# ADC.net
KiCad netlist of a schematic drawn in Altium Designer
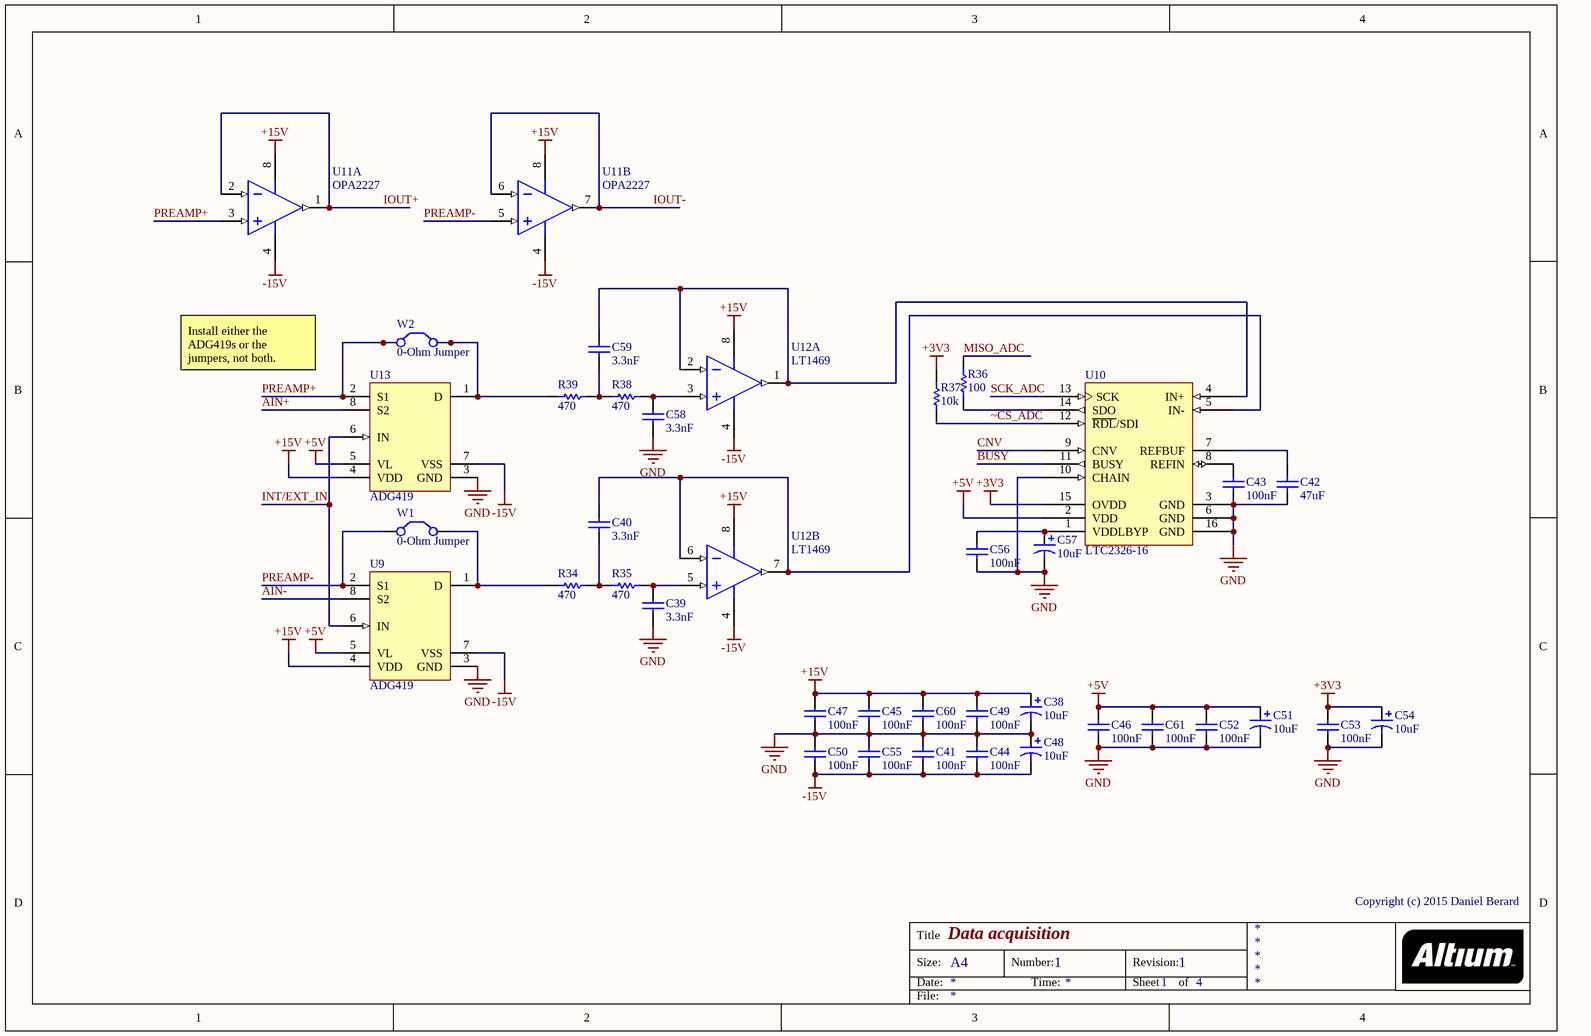
[diagram p0: ADC.SchDoc]

(export (version "E")
  (design (tool "Eeschema 10.0.6"))
  (components
    (comp (ref "C38")
      (value "10uF")
      (footprint "3528")
      (description "Polarized Capacitor (Radial)")
      (fields (field (name "PUBLISHER") "Altium Limited"))
      (libsource (lib "Miscellaneous Devices") (part "Cap Pol1"))
    )
    (comp (ref "C39")
      (value "3.3nF")
      (footprint "6-0805_N")
      (description "Capacitor")
      (fields (field (name "PUBLISHER") "Altium Limited"))
      (libsource (lib "Miscellaneous Devices") (part "Cap"))
    )
    (comp (ref "C40")
      (value "3.3nF")
      (footprint "6-0805_N")
      (description "Capacitor")
      (fields (field (name "PUBLISHER") "Altium Limited"))
      (libsource (lib "Miscellaneous Devices") (part "Cap"))
    )
    (comp (ref "C41")
      (value "100nF")
      (footprint "6-0805_N")
      (description "Capacitor")
      (fields (field (name "PUBLISHER") "Altium Limited"))
      (libsource (lib "Miscellaneous Devices") (part "Cap"))
    )
    (comp (ref "C42")
      (value "47uF")
      (footprint "C1210")
      (description "Capacitor")
      (fields (field (name "PUBLISHER") "Altium Limited"))
      (libsource (lib "Miscellaneous Devices") (part "Cap"))
    )
    (comp (ref "C43")
      (value "100nF")
      (footprint "6-0805_N")
      (description "Capacitor")
      (fields (field (name "PUBLISHER") "Altium Limited"))
      (libsource (lib "Miscellaneous Devices") (part "Cap"))
    )
    (comp (ref "C44")
      (value "100nF")
      (footprint "6-0805_N")
      (description "Capacitor")
      (fields (field (name "PUBLISHER") "Altium Limited"))
      (libsource (lib "Miscellaneous Devices") (part "Cap"))
    )
    (comp (ref "C45")
      (value "100nF")
      (footprint "6-0805_N")
      (description "Capacitor")
      (fields (field (name "PUBLISHER") "Altium Limited"))
      (libsource (lib "Miscellaneous Devices") (part "Cap"))
    )
    (comp (ref "C46")
      (value "100nF")
      (footprint "6-0805_N")
      (description "Capacitor")
      (fields (field (name "PUBLISHER") "Altium Limited"))
      (libsource (lib "Miscellaneous Devices") (part "Cap"))
    )
    (comp (ref "C47")
      (value "100nF")
      (footprint "6-0805_N")
      (description "Capacitor")
      (fields (field (name "PUBLISHER") "Altium Limited"))
      (libsource (lib "Miscellaneous Devices") (part "Cap"))
    )
    (comp (ref "C48")
      (value "10uF")
      (footprint "3528")
      (description "Polarized Capacitor (Radial)")
      (fields (field (name "PUBLISHER") "Altium Limited"))
      (libsource (lib "Miscellaneous Devices") (part "Cap Pol1"))
    )
    (comp (ref "C49")
      (value "100nF")
      (footprint "6-0805_N")
      (description "Capacitor")
      (fields (field (name "PUBLISHER") "Altium Limited"))
      (libsource (lib "Miscellaneous Devices") (part "Cap"))
    )
    (comp (ref "C50")
      (value "100nF")
      (footprint "6-0805_N")
      (description "Capacitor")
      (fields (field (name "PUBLISHER") "Altium Limited"))
      (libsource (lib "Miscellaneous Devices") (part "Cap"))
    )
    (comp (ref "C51")
      (value "10uF")
      (footprint "6-0805_N")
      (description "Polarized Capacitor (Radial)")
      (fields (field (name "PUBLISHER") "Altium Limited"))
      (libsource (lib "Miscellaneous Devices") (part "Cap Pol1"))
    )
    (comp (ref "C52")
      (value "100nF")
      (footprint "6-0805_N")
      (description "Capacitor")
      (fields (field (name "PUBLISHER") "Altium Limited"))
      (libsource (lib "Miscellaneous Devices") (part "Cap"))
    )
    (comp (ref "C53")
      (value "100nF")
      (footprint "6-0805_N")
      (description "Capacitor")
      (fields (field (name "PUBLISHER") "Altium Limited"))
      (libsource (lib "Miscellaneous Devices") (part "Cap"))
    )
    (comp (ref "C54")
      (value "10uF")
      (footprint "6-0805_N")
      (description "Polarized Capacitor (Radial)")
      (fields (field (name "PUBLISHER") "Altium Limited"))
      (libsource (lib "Miscellaneous Devices") (part "Cap Pol1"))
    )
    (comp (ref "C55")
      (value "100nF")
      (footprint "6-0805_N")
      (description "Capacitor")
      (fields (field (name "PUBLISHER") "Altium Limited"))
      (libsource (lib "Miscellaneous Devices") (part "Cap"))
    )
    (comp (ref "C56")
      (value "100nF")
      (footprint "6-0805_N")
      (description "Capacitor")
      (fields (field (name "PUBLISHER") "Altium Limited"))
      (libsource (lib "Miscellaneous Devices") (part "Cap"))
    )
    (comp (ref "C57")
      (value "10uF")
      (footprint "6-0805_N")
      (description "Polarized Capacitor (Radial)")
      (fields (field (name "PUBLISHER") "Altium Limited"))
      (libsource (lib "Miscellaneous Devices") (part "Cap Pol1"))
    )
    (comp (ref "C58")
      (value "3.3nF")
      (footprint "6-0805_N")
      (description "Capacitor")
      (fields (field (name "PUBLISHER") "Altium Limited"))
      (libsource (lib "Miscellaneous Devices") (part "Cap"))
    )
    (comp (ref "C59")
      (value "3.3nF")
      (footprint "6-0805_N")
      (description "Capacitor")
      (fields (field (name "PUBLISHER") "Altium Limited"))
      (libsource (lib "Miscellaneous Devices") (part "Cap"))
    )
    (comp (ref "C60")
      (value "100nF")
      (footprint "6-0805_N")
      (description "Capacitor")
      (fields (field (name "PUBLISHER") "Altium Limited"))
      (libsource (lib "Miscellaneous Devices") (part "Cap"))
    )
    (comp (ref "C61")
      (value "100nF")
      (footprint "6-0805_N")
      (description "Capacitor")
      (fields (field (name "PUBLISHER") "Altium Limited"))
      (libsource (lib "Miscellaneous Devices") (part "Cap"))
    )
    (comp (ref "R34")
      (value "470")
      (footprint "6-0805_N")
      (description "Resistor")
      (fields (field (name "PUBLISHER") "Altium Limited"))
      (libsource (lib "Miscellaneous Devices") (part "Res1"))
    )
    (comp (ref "R35")
      (value "470")
      (footprint "6-0805_N")
      (description "Resistor")
      (fields (field (name "PUBLISHER") "Altium Limited"))
      (libsource (lib "Miscellaneous Devices") (part "Res1"))
    )
    (comp (ref "R36")
      (value "100")
      (footprint "6-0805_N")
      (description "Resistor")
      (fields (field (name "PUBLISHER") "Altium Limited"))
      (libsource (lib "Miscellaneous Devices") (part "Res1"))
    )
    (comp (ref "R37")
      (value "10k")
      (footprint "6-0805_N")
      (description "Resistor")
      (fields (field (name "PUBLISHER") "Altium Limited"))
      (libsource (lib "Miscellaneous Devices") (part "Res1"))
    )
    (comp (ref "R38")
      (value "470")
      (footprint "6-0805_N")
      (description "Resistor")
      (fields (field (name "PUBLISHER") "Altium Limited"))
      (libsource (lib "Miscellaneous Devices") (part "Res1"))
    )
    (comp (ref "R39")
      (value "470")
      (footprint "6-0805_N")
      (description "Resistor")
      (fields (field (name "PUBLISHER") "Altium Limited"))
      (libsource (lib "Miscellaneous Devices") (part "Res1"))
    )
    (comp (ref "U9")
      (value "ADG419")
      (footprint "ADI-RM-8_N")
      (description "LC2MOS Precision Mini-DIP Analog Switches, 25 Ohm Ron, 8-pin SOP (RM-8), Tube")
      (fields (field (name "MANUFACTURER") "Analog Devices") (field (name "PARTNUMBER") "ADG419BRMZ"))
      (libsource (lib "Altium Content Vault") (part "CMP-0792-00196-1"))
    )
    (comp (ref "U10") (value "LTC2326-16") (footprint "MSOP-16") (libsource (lib "DB") (part "LTC2326-16")))
    (comp (ref "U11")
      (value "OPA2227")
      (footprint "TI-D8_N")
      (fields (field (name "MANUFACTURER") "Texas Instruments") (field (name "PARTNUMBER") "OPA2227U/2K5"))
      (libsource (lib "Altium Content Vault") (part "CMP-0272-00267-2"))
    )
    (comp (ref "U12")
      (value "LT1469")
      (footprint "LT-S8-8_N")
      (fields
        (field (name "LINEAR TECHNOLOGY PART NUMBER") "LT1469-2")
        (field (name "PARTNUMBER") "LT1469CS8-2#PBF")
        (field (name "MANUFACTURER") "Linear Technology")
      )
      (libsource (lib "Altium Content Vault") (part "CMP-0359-02956-2"))
    )
    (comp (ref "U13")
      (value "ADG419")
      (footprint "ADI-RM-8_N")
      (description "LC2MOS Precision Mini-DIP Analog Switches, 25 Ohm Ron, 8-pin SOP (RM-8), Tube")
      (fields (field (name "MANUFACTURER") "Analog Devices") (field (name "PARTNUMBER") "ADG419BRMZ"))
      (libsource (lib "Altium Content Vault") (part "CMP-0792-00196-1"))
    )
    (comp (ref "W1")
      (value "0-Ohm Jumper")
      (footprint "6-0805_N")
      (description "Jumper Wire")
      (fields (field (name "PUBLISHER") "Altium Limited"))
      (libsource (lib "Miscellaneous Devices") (part "Jumper"))
    )
    (comp (ref "W2")
      (value "0-Ohm Jumper")
      (footprint "6-0805_N")
      (description "Jumper Wire")
      (fields (field (name "PUBLISHER") "Altium Limited"))
      (libsource (lib "Miscellaneous Devices") (part "Jumper"))
    )
  )
  (nets
    (net (code "1") (name "+3V3") (class "Default")
      (node (ref "C53") (pin "2") (pinfunction "2_2") (pintype "passive"))
      (node (ref "C54") (pin "1") (pinfunction "1_1") (pintype "passive"))
      (node (ref "R37") (pin "2") (pinfunction "2_2") (pintype "passive"))
      (node (ref "U10") (pin "15") (pinfunction "OVDD_15") (pintype "power_in"))
    )
    (net (code "2") (name "+5V") (class "Default")
      (node (ref "C46") (pin "2") (pinfunction "2_2") (pintype "passive"))
      (node (ref "C51") (pin "1") (pinfunction "1_1") (pintype "passive"))
      (node (ref "C52") (pin "2") (pinfunction "2_2") (pintype "passive"))
      (node (ref "C61") (pin "2") (pinfunction "2_2") (pintype "passive"))
      (node (ref "U10") (pin "2") (pinfunction "VDD_2") (pintype "power_in"))
      (node (ref "U13") (pin "5") (pinfunction "VL_5") (pintype "power_in"))
      (node (ref "U9") (pin "5") (pinfunction "VL_5") (pintype "power_in"))
    )
    (net (code "3") (name "+15V") (class "Default")
      (node (ref "C38") (pin "1") (pinfunction "1_1") (pintype "passive"))
      (node (ref "C45") (pin "2") (pinfunction "2_2") (pintype "passive"))
      (node (ref "C47") (pin "2") (pinfunction "2_2") (pintype "passive"))
      (node (ref "C49") (pin "2") (pinfunction "2_2") (pintype "passive"))
      (node (ref "C60") (pin "2") (pinfunction "2_2") (pintype "passive"))
      (node (ref "U11") (pin "8") (pinfunction "V+_8") (pintype "power_in"))
      (node (ref "U12") (pin "8") (pinfunction "V+_8") (pintype "power_in"))
      (node (ref "U13") (pin "4") (pinfunction "VDD_4") (pintype "power_in"))
      (node (ref "U9") (pin "4") (pinfunction "VDD_4") (pintype "power_in"))
    )
    (net (code "4") (name "-15V") (class "Default")
      (node (ref "C41") (pin "1") (pinfunction "1_1") (pintype "passive"))
      (node (ref "C44") (pin "1") (pinfunction "1_1") (pintype "passive"))
      (node (ref "C48") (pin "2") (pinfunction "2_2") (pintype "passive"))
      (node (ref "C50") (pin "1") (pinfunction "1_1") (pintype "passive"))
      (node (ref "C55") (pin "1") (pinfunction "1_1") (pintype "passive"))
      (node (ref "U11") (pin "4") (pinfunction "V-_4") (pintype "power_in"))
      (node (ref "U12") (pin "4") (pinfunction "V-_4") (pintype "power_in"))
      (node (ref "U13") (pin "7") (pinfunction "VSS_7") (pintype "power_in"))
      (node (ref "U9") (pin "7") (pinfunction "VSS_7") (pintype "power_in"))
    )
    (net (code "5") (name "/AIN+") (class "Default")
      (node (ref "U13") (pin "8") (pinfunction "S2_8") (pintype "passive"))
    )
    (net (code "6") (name "/AIN-") (class "Default")
      (node (ref "U9") (pin "8") (pinfunction "S2_8") (pintype "passive"))
    )
    (net (code "7") (name "/BUSY") (class "Default")
      (node (ref "U10") (pin "11") (pinfunction "BUSY_11") (pintype "output"))
    )
    (net (code "8") (name "/CNV") (class "Default")
      (node (ref "U10") (pin "9") (pinfunction "CNV_9") (pintype "input"))
    )
    (net (code "9") (name "/INT{slash}EXT_IN") (class "Default")
      (node (ref "U13") (pin "6") (pinfunction "IN_6") (pintype "input"))
      (node (ref "U9") (pin "6") (pinfunction "IN_6") (pintype "input"))
    )
    (net (code "10") (name "/IOUT+") (class "Default")
      (node (ref "U11") (pin "1") (pinfunction "OUT_A_1") (pintype "output"))
      (node (ref "U11") (pin "2") (pinfunction "IN_A-_2") (pintype "input"))
    )
    (net (code "11") (name "/IOUT-") (class "Default")
      (node (ref "U11") (pin "6") (pinfunction "IN_B-_6") (pintype "input"))
      (node (ref "U11") (pin "7") (pinfunction "OUT_B_7") (pintype "output"))
    )
    (net (code "12") (name "/MISO_ADC") (class "Default")
      (node (ref "R36") (pin "1") (pinfunction "1_1") (pintype "passive"))
    )
    (net (code "13") (name "/PREAMP+") (class "Default")
      (node (ref "U11") (pin "3") (pinfunction "IN_A+_3") (pintype "input"))
      (node (ref "U13") (pin "2") (pinfunction "S1_2") (pintype "passive"))
      (node (ref "W2") (pin "1") (pinfunction "C1_1") (pintype "passive"))
    )
    (net (code "14") (name "/PREAMP-") (class "Default")
      (node (ref "U11") (pin "5") (pinfunction "IN_B+_5") (pintype "input"))
      (node (ref "U9") (pin "2") (pinfunction "S1_2") (pintype "passive"))
      (node (ref "W1") (pin "1") (pinfunction "C1_1") (pintype "passive"))
    )
    (net (code "15") (name "/SCK_ADC") (class "Default")
      (node (ref "U10") (pin "13") (pinfunction "SCK_13") (pintype "input"))
    )
    (net (code "16") (name "/~CS_ADC") (class "Default")
      (node (ref "R37") (pin "1") (pinfunction "1_1") (pintype "passive"))
      (node (ref "U10") (pin "12") (pinfunction "~{RDL}/SDI_12") (pintype "input"))
    )
    (net (code "17") (name "GND") (class "Default")
      (node (ref "C38") (pin "2") (pinfunction "2_2") (pintype "passive"))
      (node (ref "C39") (pin "2") (pinfunction "2_2") (pintype "passive"))
      (node (ref "C41") (pin "2") (pinfunction "2_2") (pintype "passive"))
      (node (ref "C42") (pin "1") (pinfunction "1_1") (pintype "passive"))
      (node (ref "C43") (pin "1") (pinfunction "1_1") (pintype "passive"))
      (node (ref "C44") (pin "2") (pinfunction "2_2") (pintype "passive"))
      (node (ref "C45") (pin "1") (pinfunction "1_1") (pintype "passive"))
      (node (ref "C46") (pin "1") (pinfunction "1_1") (pintype "passive"))
      (node (ref "C47") (pin "1") (pinfunction "1_1") (pintype "passive"))
      (node (ref "C48") (pin "1") (pinfunction "1_1") (pintype "passive"))
      (node (ref "C49") (pin "1") (pinfunction "1_1") (pintype "passive"))
      (node (ref "C50") (pin "2") (pinfunction "2_2") (pintype "passive"))
      (node (ref "C51") (pin "2") (pinfunction "2_2") (pintype "passive"))
      (node (ref "C52") (pin "1") (pinfunction "1_1") (pintype "passive"))
      (node (ref "C53") (pin "1") (pinfunction "1_1") (pintype "passive"))
      (node (ref "C54") (pin "2") (pinfunction "2_2") (pintype "passive"))
      (node (ref "C55") (pin "2") (pinfunction "2_2") (pintype "passive"))
      (node (ref "C56") (pin "1") (pinfunction "1_1") (pintype "passive"))
      (node (ref "C57") (pin "2") (pinfunction "2_2") (pintype "passive"))
      (node (ref "C58") (pin "2") (pinfunction "2_2") (pintype "passive"))
      (node (ref "C60") (pin "1") (pinfunction "1_1") (pintype "passive"))
      (node (ref "C61") (pin "1") (pinfunction "1_1") (pintype "passive"))
      (node (ref "U10") (pin "10") (pinfunction "CHAIN_10") (pintype "input"))
      (node (ref "U10") (pin "16") (pinfunction "GND_16") (pintype "power_in"))
      (node (ref "U10") (pin "3") (pinfunction "GND_3") (pintype "power_in"))
      (node (ref "U10") (pin "6") (pinfunction "GND_6") (pintype "power_in"))
      (node (ref "U13") (pin "3") (pinfunction "GND_3") (pintype "power_in"))
      (node (ref "U9") (pin "3") (pinfunction "GND_3") (pintype "power_in"))
    )
    (net (code "18") (name "Net-(C40-Pad2)") (class "Default")
      (node (ref "C40") (pin "2") (pinfunction "2_2") (pintype "passive"))
      (node (ref "R34") (pin "2") (pinfunction "2_2") (pintype "passive"))
      (node (ref "R35") (pin "1") (pinfunction "1_1") (pintype "passive"))
    )
    (net (code "19") (name "Net-(C59-Pad2)") (class "Default")
      (node (ref "C59") (pin "2") (pinfunction "2_2") (pintype "passive"))
      (node (ref "R38") (pin "1") (pinfunction "1_1") (pintype "passive"))
      (node (ref "R39") (pin "2") (pinfunction "2_2") (pintype "passive"))
    )
    (net (code "20") (name "Net-(U9-D)") (class "Default")
      (node (ref "R34") (pin "1") (pinfunction "1_1") (pintype "passive"))
      (node (ref "U9") (pin "1") (pinfunction "D_1") (pintype "passive"))
      (node (ref "W1") (pin "2") (pinfunction "C2_2") (pintype "passive"))
    )
    (net (code "21") (name "Net-(U10-IN+)") (class "Default")
      (node (ref "C59") (pin "1") (pinfunction "1_1") (pintype "passive"))
      (node (ref "U10") (pin "4") (pinfunction "IN+_4") (pintype "input"))
      (node (ref "U12") (pin "1") (pinfunction "OUT_A_1") (pintype "output"))
      (node (ref "U12") (pin "2") (pinfunction "-IN_A_2") (pintype "input"))
    )
    (net (code "22") (name "Net-(U10-IN-)") (class "Default")
      (node (ref "C40") (pin "1") (pinfunction "1_1") (pintype "passive"))
      (node (ref "U10") (pin "5") (pinfunction "IN-_5") (pintype "input"))
      (node (ref "U12") (pin "6") (pinfunction "-IN_B_6") (pintype "input"))
      (node (ref "U12") (pin "7") (pinfunction "OUT_B_7") (pintype "output"))
    )
    (net (code "23") (name "Net-(U10-REFBUF)") (class "Default")
      (node (ref "C42") (pin "2") (pinfunction "2_2") (pintype "passive"))
      (node (ref "U10") (pin "7") (pinfunction "REFBUF_7") (pintype "passive"))
    )
    (net (code "24") (name "Net-(U10-REFIN)") (class "Default")
      (node (ref "C43") (pin "2") (pinfunction "2_2") (pintype "passive"))
      (node (ref "U10") (pin "8") (pinfunction "REFIN_8") (pintype "bidirectional"))
    )
    (net (code "25") (name "Net-(U10-SDO)") (class "Default")
      (node (ref "R36") (pin "2") (pinfunction "2_2") (pintype "passive"))
      (node (ref "U10") (pin "14") (pinfunction "SDO_14") (pintype "output"))
    )
    (net (code "26") (name "Net-(U10-VDDLBYP)") (class "Default")
      (node (ref "C56") (pin "2") (pinfunction "2_2") (pintype "passive"))
      (node (ref "C57") (pin "1") (pinfunction "1_1") (pintype "passive"))
      (node (ref "U10") (pin "1") (pinfunction "VDDLBYP_1") (pintype "passive"))
    )
    (net (code "27") (name "Net-(U12A-+IN_A)") (class "Default")
      (node (ref "C58") (pin "1") (pinfunction "1_1") (pintype "passive"))
      (node (ref "R38") (pin "2") (pinfunction "2_2") (pintype "passive"))
      (node (ref "U12") (pin "3") (pinfunction "+IN_A_3") (pintype "input"))
    )
    (net (code "28") (name "Net-(U12B-+IN_B)") (class "Default")
      (node (ref "C39") (pin "1") (pinfunction "1_1") (pintype "passive"))
      (node (ref "R35") (pin "2") (pinfunction "2_2") (pintype "passive"))
      (node (ref "U12") (pin "5") (pinfunction "+IN_B_5") (pintype "input"))
    )
    (net (code "29") (name "Net-(U13-D)") (class "Default")
      (node (ref "R39") (pin "1") (pinfunction "1_1") (pintype "passive"))
      (node (ref "U13") (pin "1") (pinfunction "D_1") (pintype "passive"))
      (node (ref "W2") (pin "2") (pinfunction "C2_2") (pintype "passive"))
    )
  )
)
